# LEDController.net
KiCad netlist of a schematic drawn in EAGLE
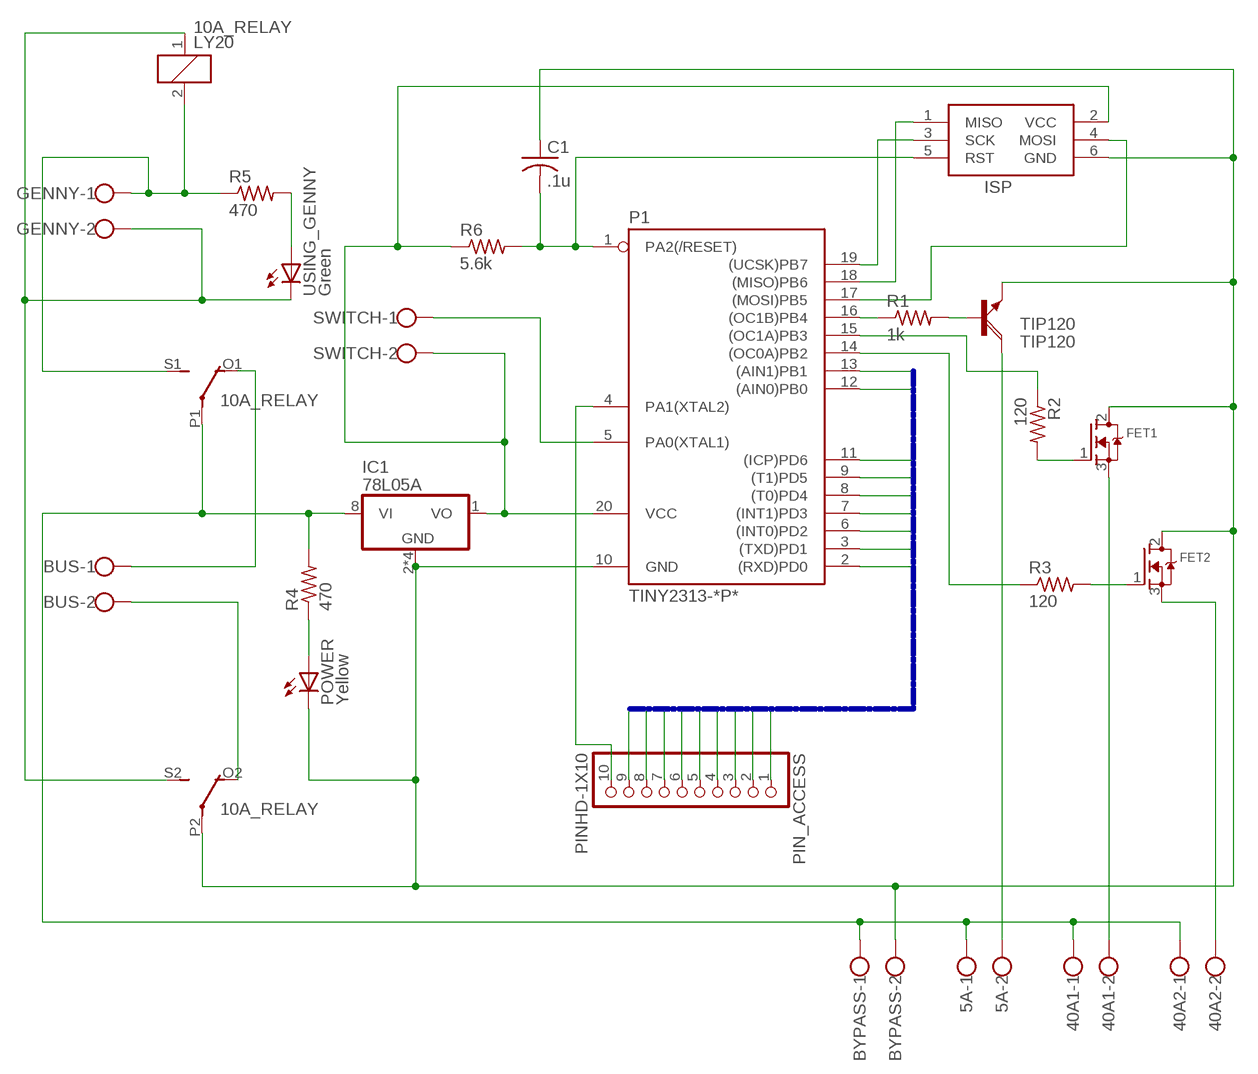
[diagram p0: schematic, sheet 1]

(export (version "E")
  (design (tool "Eeschema 10.0.6"))
  (components
    (comp (ref "5A")
      (value "W237-102")
      (footprint "eagle-import:W237-102")
      (fields (field (name "MPN") "237-102"))
      (libsource (lib "eagle-import") (part "W237-102"))
    )
    (comp (ref "10A_RELAY")
      (value "LY20")
      (footprint "eagle-import:LY20")
      (libsource (lib "eagle-import") (part "LY20"))
    )
    (comp (ref "40A1")
      (value "W237-102")
      (footprint "eagle-import:W237-102")
      (fields (field (name "MPN") "237-102"))
      (libsource (lib "eagle-import") (part "W237-102"))
    )
    (comp (ref "40A2")
      (value "W237-102")
      (footprint "eagle-import:W237-102")
      (fields (field (name "MPN") "237-102"))
      (libsource (lib "eagle-import") (part "W237-102"))
    )
    (comp (ref "BUS")
      (value "W237-102")
      (footprint "eagle-import:W237-102")
      (fields (field (name "MPN") "237-102"))
      (libsource (lib "eagle-import") (part "W237-102"))
    )
    (comp (ref "BYPASS")
      (value "W237-102")
      (footprint "eagle-import:W237-102")
      (fields (field (name "MPN") "237-102"))
      (libsource (lib "eagle-import") (part "W237-102"))
    )
    (comp (ref "C1")
      (value ".1u")
      (footprint "eagle-import:C025-030X050")
      (libsource (lib "eagle-import") (part "C-US025-030X050"))
    )
    (comp (ref "FET1")
      (value "MOSFET-NGDS_TO220V")
      (footprint "eagle-import:TO220V")
      (libsource (lib "eagle-import") (part "MOSFET-NGDS_TO220V"))
    )
    (comp (ref "FET2")
      (value "MOSFET-NGDS_TO220V")
      (footprint "eagle-import:TO220V")
      (libsource (lib "eagle-import") (part "MOSFET-NGDS_TO220V"))
    )
    (comp (ref "GENNY")
      (value "W237-102")
      (footprint "eagle-import:W237-102")
      (fields (field (name "MPN") "237-102"))
      (libsource (lib "eagle-import") (part "W237-102"))
    )
    (comp (ref "IC1")
      (value "78L05A")
      (footprint "eagle-import:SOIC8")
      (libsource (lib "eagle-import") (part "78AL05"))
    )
    (comp (ref "ISP")
      (value "AVRISP-6")
      (footprint "eagle-import:AVRISP")
      (libsource (lib "eagle-import") (part "AVRISP-6"))
    )
    (comp (ref "P1")
      (value "TINY2313-*P*")
      (footprint "eagle-import:DIL20")
      (libsource (lib "eagle-import") (part "TINY2313-P"))
    )
    (comp (ref "PIN_ACCESS")
      (value "PINHD-1X10")
      (footprint "eagle-import:1X10-BIG")
      (libsource (lib "eagle-import") (part "PINHD-1X10"))
    )
    (comp (ref "POWER")
      (value "Yellow")
      (footprint "eagle-import:LED5MM")
      (libsource (lib "eagle-import") (part "LED5MM"))
    )
    (comp (ref "R1")
      (value "1k")
      (footprint "eagle-import:0204_7")
      (libsource (lib "eagle-import") (part "R-US_0204/7"))
    )
    (comp (ref "R2")
      (value "120")
      (footprint "eagle-import:0204_7")
      (libsource (lib "eagle-import") (part "R-US_0204/7"))
    )
    (comp (ref "R3")
      (value "120")
      (footprint "eagle-import:0204_7")
      (libsource (lib "eagle-import") (part "R-US_0204/7"))
    )
    (comp (ref "R4")
      (value "470")
      (footprint "eagle-import:0204_7")
      (libsource (lib "eagle-import") (part "R-US_0204/7"))
    )
    (comp (ref "R5")
      (value "470")
      (footprint "eagle-import:0204_7")
      (libsource (lib "eagle-import") (part "R-US_0204/7"))
    )
    (comp (ref "R6")
      (value "5.6k")
      (footprint "eagle-import:0204_7")
      (libsource (lib "eagle-import") (part "R-US_0204/7"))
    )
    (comp (ref "SWITCH")
      (value "W237-102")
      (footprint "eagle-import:W237-102")
      (fields (field (name "MPN") "237-102"))
      (libsource (lib "eagle-import") (part "W237-102"))
    )
    (comp (ref "TIP120")
      (value "TIP120")
      (footprint "eagle-import:TO220AH")
      (libsource (lib "eagle-import") (part "TIP120"))
    )
    (comp (ref "USING_GENNY")
      (value "Green")
      (footprint "eagle-import:LED5MM")
      (libsource (lib "eagle-import") (part "LED5MM"))
    )
  )
  (nets
    (net (code "1") (name "/PIN1") (class "Default")
      (node (ref "P1") (pin "2") (pinfunction "(RXD)PD0_2") (pintype "bidirectional"))
      (node (ref "PIN_ACCESS") (pin "1") (pinfunction "1_1") (pintype "passive"))
    )
    (net (code "2") (name "/PIN2") (class "Default")
      (node (ref "P1") (pin "3") (pinfunction "(TXD)PD1_3") (pintype "bidirectional"))
      (node (ref "PIN_ACCESS") (pin "2") (pinfunction "2_2") (pintype "passive"))
    )
    (net (code "3") (name "/PIN3") (class "Default")
      (node (ref "P1") (pin "12") (pinfunction "(AIN0)PB0_12") (pintype "bidirectional"))
      (node (ref "PIN_ACCESS") (pin "3") (pinfunction "3_3") (pintype "passive"))
    )
    (net (code "4") (name "/PIN4") (class "Default")
      (node (ref "P1") (pin "13") (pinfunction "(AIN1)PB1_13") (pintype "bidirectional"))
      (node (ref "PIN_ACCESS") (pin "4") (pinfunction "4_4") (pintype "passive"))
    )
    (net (code "5") (name "/PIN5") (class "Default")
      (node (ref "P1") (pin "6") (pinfunction "(INT0)PD2_6") (pintype "bidirectional"))
      (node (ref "PIN_ACCESS") (pin "5") (pinfunction "5_5") (pintype "passive"))
    )
    (net (code "6") (name "/PIN6") (class "Default")
      (node (ref "P1") (pin "7") (pinfunction "(INT1)PD3_7") (pintype "bidirectional"))
      (node (ref "PIN_ACCESS") (pin "6") (pinfunction "6_6") (pintype "passive"))
    )
    (net (code "7") (name "/PIN7") (class "Default")
      (node (ref "P1") (pin "8") (pinfunction "(T0)PD4_8") (pintype "bidirectional"))
      (node (ref "PIN_ACCESS") (pin "7") (pinfunction "7_7") (pintype "passive"))
    )
    (net (code "8") (name "/PIN8") (class "Default")
      (node (ref "P1") (pin "9") (pinfunction "(T1)PD5_9") (pintype "bidirectional"))
      (node (ref "PIN_ACCESS") (pin "8") (pinfunction "8_8") (pintype "passive"))
    )
    (net (code "9") (name "/PIN9") (class "Default")
      (node (ref "P1") (pin "11") (pinfunction "(ICP)PD6_11") (pintype "bidirectional"))
      (node (ref "PIN_ACCESS") (pin "9") (pinfunction "9_9") (pintype "passive"))
    )
    (net (code "10") (name "Net-(5AB-KL)") (class "Default")
      (node (ref "5A") (pin "2") (pinfunction "KL_2") (pintype "passive"))
      (node (ref "TIP120") (pin "C") (pinfunction "C_C") (pintype "passive"))
    )
    (net (code "11") (name "Net-(10A_RELAYB-O)") (class "Default")
      (node (ref "10A_RELAY") (pin "O1") (pinfunction "O_O1") (pintype "passive"))
      (node (ref "BUS") (pin "1") (pinfunction "KL_1") (pintype "passive"))
    )
    (net (code "12") (name "Net-(10A_RELAYB-P)") (class "Default")
      (node (ref "10A_RELAY") (pin "P1") (pinfunction "P_P1") (pintype "passive"))
      (node (ref "40A1") (pin "1") (pinfunction "KL_1") (pintype "passive"))
      (node (ref "40A2") (pin "1") (pinfunction "KL_1") (pintype "passive"))
      (node (ref "5A") (pin "1") (pinfunction "KL_1") (pintype "passive"))
      (node (ref "BYPASS") (pin "1") (pinfunction "KL_1") (pintype "passive"))
      (node (ref "IC1") (pin "8") (pinfunction "VI_8") (pintype "input"))
      (node (ref "R4") (pin "2") (pinfunction "2_2") (pintype "passive"))
    )
    (net (code "13") (name "Net-(10A_RELAYB-S)") (class "Default")
      (node (ref "10A_RELAY") (pin "2") (pinfunction "2_2") (pintype "passive"))
      (node (ref "10A_RELAY") (pin "S1") (pinfunction "S_S1") (pintype "passive"))
      (node (ref "GENNY") (pin "1") (pinfunction "KL_1") (pintype "passive"))
      (node (ref "R5") (pin "1") (pinfunction "1_1") (pintype "passive"))
    )
    (net (code "14") (name "Net-(10A_RELAYC-O)") (class "Default")
      (node (ref "10A_RELAY") (pin "O2") (pinfunction "O_O2") (pintype "passive"))
      (node (ref "BUS") (pin "2") (pinfunction "KL_2") (pintype "passive"))
    )
    (net (code "15") (name "Net-(10A_RELAYC-P)") (class "Default")
      (node (ref "10A_RELAY") (pin "P2") (pinfunction "P_P2") (pintype "passive"))
      (node (ref "BYPASS") (pin "2") (pinfunction "KL_2") (pintype "passive"))
      (node (ref "C1") (pin "1") (pinfunction "1_1") (pintype "passive"))
      (node (ref "FET1") (pin "2") (pinfunction "D_2") (pintype "bidirectional"))
      (node (ref "FET2") (pin "2") (pinfunction "D_2") (pintype "bidirectional"))
      (node (ref "IC1") (pin "2") (pinfunction "GND_2") (pintype "passive"))
      (node (ref "IC1") (pin "3") (pinfunction "GND_3") (pintype "passive"))
      (node (ref "IC1") (pin "6") (pinfunction "GND_6") (pintype "passive"))
      (node (ref "IC1") (pin "7") (pinfunction "GND_7") (pintype "passive"))
      (node (ref "ISP") (pin "6") (pinfunction "GND_6") (pintype "power_in"))
      (node (ref "P1") (pin "10") (pinfunction "GND_10") (pintype "power_in"))
      (node (ref "POWER") (pin "K") (pinfunction "C_K") (pintype "passive"))
      (node (ref "TIP120") (pin "E") (pinfunction "E_E") (pintype "passive"))
    )
    (net (code "16") (name "Net-(10A_RELAYC-S)") (class "Default")
      (node (ref "10A_RELAY") (pin "1") (pinfunction "1_1") (pintype "passive"))
      (node (ref "10A_RELAY") (pin "S2") (pinfunction "S_S2") (pintype "passive"))
      (node (ref "GENNY") (pin "2") (pinfunction "KL_2") (pintype "passive"))
      (node (ref "USING_GENNY") (pin "K") (pinfunction "C_K") (pintype "passive"))
    )
    (net (code "17") (name "Net-(40A1B-KL)") (class "Default")
      (node (ref "40A1") (pin "2") (pinfunction "KL_2") (pintype "passive"))
      (node (ref "FET1") (pin "3") (pinfunction "S_3") (pintype "bidirectional"))
    )
    (net (code "18") (name "Net-(40A2B-KL)") (class "Default")
      (node (ref "40A2") (pin "2") (pinfunction "KL_2") (pintype "passive"))
      (node (ref "FET2") (pin "3") (pinfunction "S_3") (pintype "bidirectional"))
    )
    (net (code "19") (name "Net-(FET1-G)") (class "Default")
      (node (ref "FET1") (pin "1") (pinfunction "G_1") (pintype "bidirectional"))
      (node (ref "R2") (pin "2") (pinfunction "2_2") (pintype "passive"))
    )
    (net (code "20") (name "Net-(FET2-G)") (class "Default")
      (node (ref "FET2") (pin "1") (pinfunction "G_1") (pintype "bidirectional"))
      (node (ref "R3") (pin "2") (pinfunction "2_2") (pintype "passive"))
    )
    (net (code "21") (name "Net-(IC1-VO)") (class "Default")
      (node (ref "IC1") (pin "1") (pinfunction "VO_1") (pintype "passive"))
      (node (ref "ISP") (pin "2") (pinfunction "VCC_2") (pintype "power_in"))
      (node (ref "P1") (pin "20") (pinfunction "VCC_20") (pintype "power_in"))
      (node (ref "R6") (pin "1") (pinfunction "1_1") (pintype "passive"))
      (node (ref "SWITCH") (pin "2") (pinfunction "KL_2") (pintype "passive"))
    )
    (net (code "22") (name "Net-(ISP-MISO)") (class "Default")
      (node (ref "ISP") (pin "1") (pinfunction "MISO_1") (pintype "input"))
      (node (ref "P1") (pin "18") (pinfunction "(MISO)PB6_18") (pintype "bidirectional"))
    )
    (net (code "23") (name "Net-(ISP-MOSI)") (class "Default")
      (node (ref "ISP") (pin "4") (pinfunction "MOSI_4") (pintype "output"))
      (node (ref "P1") (pin "17") (pinfunction "(MOSI)PB5_17") (pintype "bidirectional"))
    )
    (net (code "24") (name "Net-(ISP-RST)") (class "Default")
      (node (ref "C1") (pin "2") (pinfunction "2_2") (pintype "passive"))
      (node (ref "ISP") (pin "5") (pinfunction "RST_5") (pintype "output"))
      (node (ref "P1") (pin "1") (pinfunction "PA2(/RESET)_1") (pintype "input"))
      (node (ref "R6") (pin "2") (pinfunction "2_2") (pintype "passive"))
    )
    (net (code "25") (name "Net-(ISP-SCK)") (class "Default")
      (node (ref "ISP") (pin "3") (pinfunction "SCK_3") (pintype "output"))
      (node (ref "P1") (pin "19") (pinfunction "(UCSK)PB7_19") (pintype "bidirectional"))
    )
    (net (code "26") (name "Net-(P1-(OC0A)PB2)") (class "Default")
      (node (ref "P1") (pin "14") (pinfunction "(OC0A)PB2_14") (pintype "bidirectional"))
      (node (ref "R3") (pin "1") (pinfunction "1_1") (pintype "passive"))
    )
    (net (code "27") (name "Net-(P1-(OC1A)PB3)") (class "Default")
      (node (ref "P1") (pin "15") (pinfunction "(OC1A)PB3_15") (pintype "bidirectional"))
      (node (ref "R2") (pin "1") (pinfunction "1_1") (pintype "passive"))
    )
    (net (code "28") (name "Net-(P1-(OC1B)PB4)") (class "Default")
      (node (ref "P1") (pin "16") (pinfunction "(OC1B)PB4_16") (pintype "bidirectional"))
      (node (ref "R1") (pin "1") (pinfunction "1_1") (pintype "passive"))
    )
    (net (code "29") (name "Net-(P1-PA0(XTAL1))") (class "Default")
      (node (ref "P1") (pin "5") (pinfunction "PA0(XTAL1)_5") (pintype "bidirectional"))
      (node (ref "SWITCH") (pin "1") (pinfunction "KL_1") (pintype "passive"))
    )
    (net (code "30") (name "Net-(P1-PA1(XTAL2))") (class "Default")
      (node (ref "P1") (pin "4") (pinfunction "PA1(XTAL2)_4") (pintype "bidirectional"))
      (node (ref "PIN_ACCESS") (pin "10") (pinfunction "10_10") (pintype "passive"))
    )
    (net (code "31") (name "Net-(POWER-PadA)") (class "Default")
      (node (ref "POWER") (pin "A") (pinfunction "A_A") (pintype "passive"))
      (node (ref "R4") (pin "1") (pinfunction "1_1") (pintype "passive"))
    )
    (net (code "32") (name "Net-(R1-Pad2)") (class "Default")
      (node (ref "R1") (pin "2") (pinfunction "2_2") (pintype "passive"))
      (node (ref "TIP120") (pin "B") (pinfunction "B_B") (pintype "passive"))
    )
    (net (code "33") (name "Net-(R5-Pad2)") (class "Default")
      (node (ref "R5") (pin "2") (pinfunction "2_2") (pintype "passive"))
      (node (ref "USING_GENNY") (pin "A") (pinfunction "A_A") (pintype "passive"))
    )
  )
)
